# melvins_board.net
KiCad netlist of a schematic drawn in EAGLE
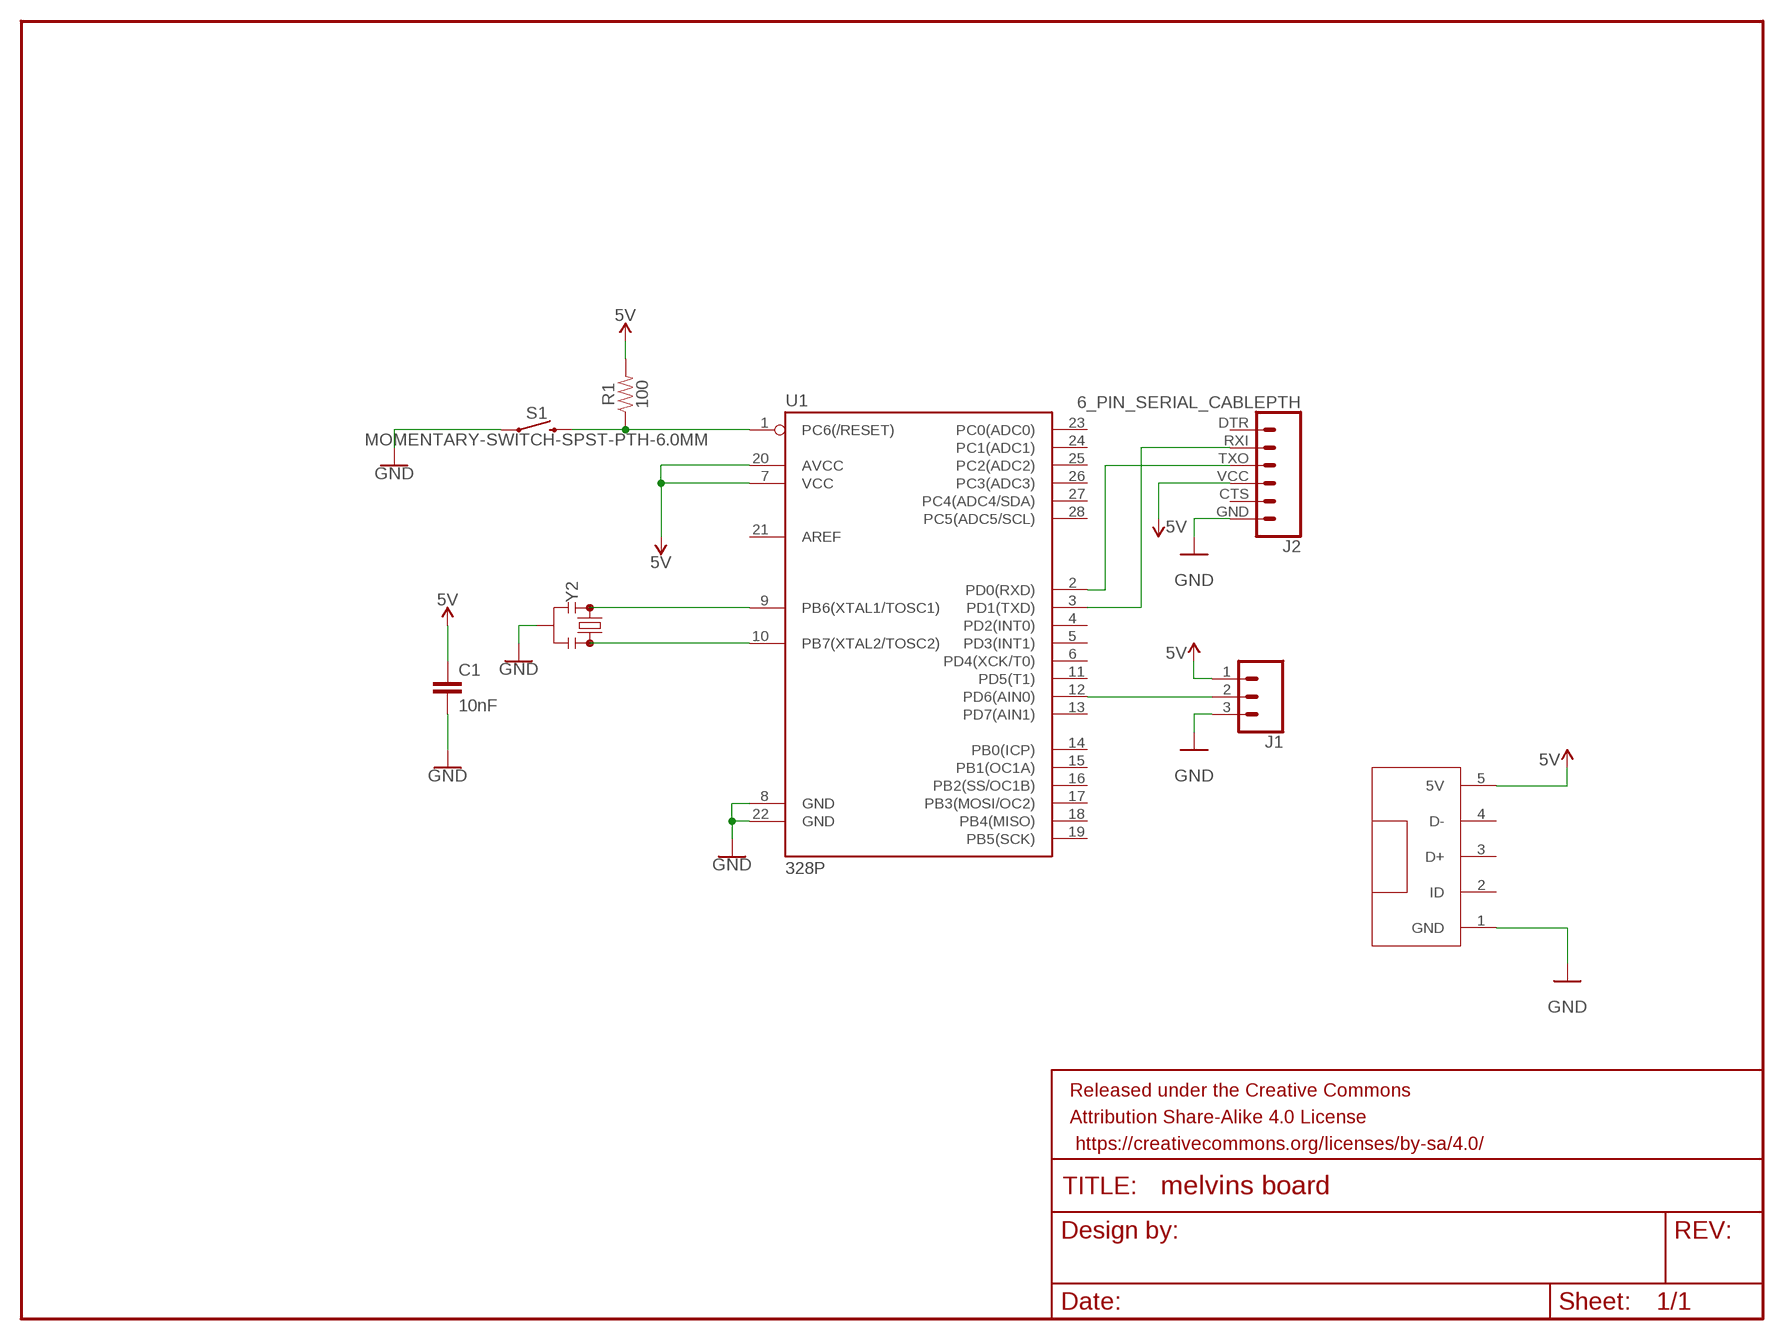
[diagram p0: schematic, sheet 1]

(export (version "E")
  (design (tool "Eeschema 10.0.6"))
  (components
    (comp (ref "C1")
      (value "10nF")
      (footprint "eagle-import:CAP-PTH-10MM")
      (libsource (lib "eagle-import") (part "10NF-PTH-10MM-10000V-1-%"))
    )
    (comp (ref "FRAME1")
      (value "FRAME-LETTER")
      (footprint "eagle-import:CREATIVE_COMMONS")
      (libsource (lib "eagle-import") (part "FRAME-LETTER"))
    )
    (comp (ref "J1")
      (value "CONN_03")
      (footprint "eagle-import:1X03")
      (libsource (lib "eagle-import") (part "CONN_03"))
    )
    (comp (ref "J2")
      (value "6_PIN_SERIAL_CABLEPTH")
      (footprint "eagle-import:FTDI_BASIC")
      (libsource (lib "eagle-import") (part "6_PIN_SERIAL_CABLEPTH"))
    )
    (comp (ref "R1")
      (value "100")
      (footprint "eagle-import:AXIAL-0.3")
      (libsource (lib "eagle-import") (part "100OHM-HORIZ-1/4W-1%"))
    )
    (comp (ref "S1")
      (value "MOMENTARY-SWITCH-SPST-PTH-6.0MM")
      (footprint "eagle-import:TACTILE_SWITCH_PTH_6.0MM")
      (libsource (lib "eagle-import") (part "MOMENTARY-SWITCH-SPST-PTH-6.0MM"))
    )
    (comp (ref "U$1")
      (value "USBPORT")
      (footprint "eagle-import:USB")
      (libsource (lib "eagle-import") (part "USBPORT"))
    )
    (comp (ref "U1")
      (value "328P")
      (footprint "eagle-import:DIP28")
      (libsource (lib "eagle-import") (part "ATMEGA328P_PDIP"))
    )
    (comp (ref "Y2")
      (value "RESONATORPTH-7.6X3.8")
      (footprint "eagle-import:RESONATOR-PTH-7.6X3.8")
      (libsource (lib "eagle-import") (part "RESONATORPTH-7.6X3.8"))
    )
  )
  (nets
    (net (code "1") (name "5V") (class "Default")
      (node (ref "C1") (pin "1") (pinfunction "1_1") (pintype "passive"))
      (node (ref "J1") (pin "1") (pinfunction "1_1") (pintype "passive"))
      (node (ref "J2") (pin "VCC") (pinfunction "4_VCC") (pintype "passive"))
      (node (ref "R1") (pin "P$2") (pinfunction "2_P$2") (pintype "passive"))
      (node (ref "U$1") (pin "5") (pinfunction "5V_5") (pintype "bidirectional"))
      (node (ref "U1") (pin "20") (pinfunction "AVCC_20") (pintype "bidirectional"))
      (node (ref "U1") (pin "7") (pinfunction "VCC_7") (pintype "bidirectional"))
    )
    (net (code "2") (name "GND") (class "Default")
      (node (ref "C1") (pin "2") (pinfunction "2_2") (pintype "passive"))
      (node (ref "J1") (pin "3") (pinfunction "3_3") (pintype "passive"))
      (node (ref "J2") (pin "GND") (pinfunction "6_GND") (pintype "passive"))
      (node (ref "S1") (pin "1") (pinfunction "1_1") (pintype "passive"))
      (node (ref "U$1") (pin "1") (pinfunction "GND_1") (pintype "bidirectional"))
      (node (ref "U1") (pin "22") (pinfunction "GND_22") (pintype "bidirectional"))
      (node (ref "U1") (pin "8") (pinfunction "GND_8") (pintype "bidirectional"))
      (node (ref "Y2") (pin "2") (pinfunction "2_2") (pintype "passive"))
    )
    (net (code "3") (name "Net-(J2-2)") (class "Default")
      (node (ref "J2") (pin "RXI") (pinfunction "2_RXI") (pintype "passive"))
      (node (ref "U1") (pin "3") (pinfunction "PD1(TXD)_3") (pintype "bidirectional"))
    )
    (net (code "4") (name "Net-(J2-3)") (class "Default")
      (node (ref "J2") (pin "TXO") (pinfunction "3_TXO") (pintype "passive"))
      (node (ref "U1") (pin "2") (pinfunction "PD0(RXD)_2") (pintype "bidirectional"))
    )
    (net (code "5") (name "Net-(R1-1)") (class "Default")
      (node (ref "R1") (pin "P$1") (pinfunction "1_P$1") (pintype "passive"))
      (node (ref "S1") (pin "3") (pinfunction "2_3") (pintype "passive"))
      (node (ref "U1") (pin "1") (pinfunction "PC6(/RESET)_1") (pintype "bidirectional"))
    )
    (net (code "6") (name "Net-(U1-PB6(XTAL1{slash}TOSC1))") (class "Default")
      (node (ref "U1") (pin "9") (pinfunction "PB6(XTAL1/TOSC1)_9") (pintype "bidirectional"))
      (node (ref "Y2") (pin "1") (pinfunction "1_1") (pintype "passive"))
    )
    (net (code "7") (name "Net-(U1-PB7(XTAL2{slash}TOSC2))") (class "Default")
      (node (ref "U1") (pin "10") (pinfunction "PB7(XTAL2/TOSC2)_10") (pintype "bidirectional"))
      (node (ref "Y2") (pin "3") (pinfunction "3_3") (pintype "passive"))
    )
    (net (code "8") (name "Net-(U1-PD6(AIN0))") (class "Default")
      (node (ref "J1") (pin "2") (pinfunction "2_2") (pintype "passive"))
      (node (ref "U1") (pin "12") (pinfunction "PD6(AIN0)_12") (pintype "bidirectional"))
    )
    (net (code "9") (name "unconnected-(J2-1-PadDTR)") (class "Default")
      (node (ref "J2") (pin "DTR") (pinfunction "1_DTR") (pintype "passive"))
    )
    (net (code "10") (name "unconnected-(J2-5-PadCTS)") (class "Default")
      (node (ref "J2") (pin "CTS") (pinfunction "5_CTS") (pintype "passive"))
    )
    (net (code "11") (name "unconnected-(U$1-D+-Pad3)") (class "Default")
      (node (ref "U$1") (pin "3") (pinfunction "D+_3") (pintype "bidirectional"))
    )
    (net (code "12") (name "unconnected-(U$1-D--Pad4)") (class "Default")
      (node (ref "U$1") (pin "4") (pinfunction "D-_4") (pintype "bidirectional"))
    )
    (net (code "13") (name "unconnected-(U$1-ID-Pad2)") (class "Default")
      (node (ref "U$1") (pin "2") (pinfunction "ID_2") (pintype "bidirectional"))
    )
    (net (code "14") (name "unconnected-(U1-AREF-Pad21)") (class "Default")
      (node (ref "U1") (pin "21") (pinfunction "AREF_21") (pintype "bidirectional"))
    )
    (net (code "15") (name "unconnected-(U1-PB0(ICP)-Pad14)") (class "Default")
      (node (ref "U1") (pin "14") (pinfunction "PB0(ICP)_14") (pintype "bidirectional"))
    )
    (net (code "16") (name "unconnected-(U1-PB1(OC1A)-Pad15)") (class "Default")
      (node (ref "U1") (pin "15") (pinfunction "PB1(OC1A)_15") (pintype "bidirectional"))
    )
    (net (code "17") (name "unconnected-(U1-PB2(SS{slash}OC1B)-Pad16)") (class "Default")
      (node (ref "U1") (pin "16") (pinfunction "PB2(SS/OC1B)_16") (pintype "bidirectional"))
    )
    (net (code "18") (name "unconnected-(U1-PB3(MOSI{slash}OC2)-Pad17)") (class "Default")
      (node (ref "U1") (pin "17") (pinfunction "PB3(MOSI/OC2)_17") (pintype "bidirectional"))
    )
    (net (code "19") (name "unconnected-(U1-PB4(MISO)-Pad18)") (class "Default")
      (node (ref "U1") (pin "18") (pinfunction "PB4(MISO)_18") (pintype "bidirectional"))
    )
    (net (code "20") (name "unconnected-(U1-PB5(SCK)-Pad19)") (class "Default")
      (node (ref "U1") (pin "19") (pinfunction "PB5(SCK)_19") (pintype "bidirectional"))
    )
    (net (code "21") (name "unconnected-(U1-PC0(ADC0)-Pad23)") (class "Default")
      (node (ref "U1") (pin "23") (pinfunction "PC0(ADC0)_23") (pintype "bidirectional"))
    )
    (net (code "22") (name "unconnected-(U1-PC1(ADC1)-Pad24)") (class "Default")
      (node (ref "U1") (pin "24") (pinfunction "PC1(ADC1)_24") (pintype "bidirectional"))
    )
    (net (code "23") (name "unconnected-(U1-PC2(ADC2)-Pad25)") (class "Default")
      (node (ref "U1") (pin "25") (pinfunction "PC2(ADC2)_25") (pintype "bidirectional"))
    )
    (net (code "24") (name "unconnected-(U1-PC3(ADC3)-Pad26)") (class "Default")
      (node (ref "U1") (pin "26") (pinfunction "PC3(ADC3)_26") (pintype "bidirectional"))
    )
    (net (code "25") (name "unconnected-(U1-PC4(ADC4{slash}SDA)-Pad27)") (class "Default")
      (node (ref "U1") (pin "27") (pinfunction "PC4(ADC4/SDA)_27") (pintype "bidirectional"))
    )
    (net (code "26") (name "unconnected-(U1-PC5(ADC5{slash}SCL)-Pad28)") (class "Default")
      (node (ref "U1") (pin "28") (pinfunction "PC5(ADC5/SCL)_28") (pintype "bidirectional"))
    )
    (net (code "27") (name "unconnected-(U1-PD2(INT0)-Pad4)") (class "Default")
      (node (ref "U1") (pin "4") (pinfunction "PD2(INT0)_4") (pintype "bidirectional"))
    )
    (net (code "28") (name "unconnected-(U1-PD3(INT1)-Pad5)") (class "Default")
      (node (ref "U1") (pin "5") (pinfunction "PD3(INT1)_5") (pintype "bidirectional"))
    )
    (net (code "29") (name "unconnected-(U1-PD4(XCK{slash}T0)-Pad6)") (class "Default")
      (node (ref "U1") (pin "6") (pinfunction "PD4(XCK/T0)_6") (pintype "bidirectional"))
    )
    (net (code "30") (name "unconnected-(U1-PD5(T1)-Pad11)") (class "Default")
      (node (ref "U1") (pin "11") (pinfunction "PD5(T1)_11") (pintype "bidirectional"))
    )
    (net (code "31") (name "unconnected-(U1-PD7(AIN1)-Pad13)") (class "Default")
      (node (ref "U1") (pin "13") (pinfunction "PD7(AIN1)_13") (pintype "bidirectional"))
    )
  )
)
